# Sheet1.net
KiCad netlist of a schematic drawn in Altium Designer
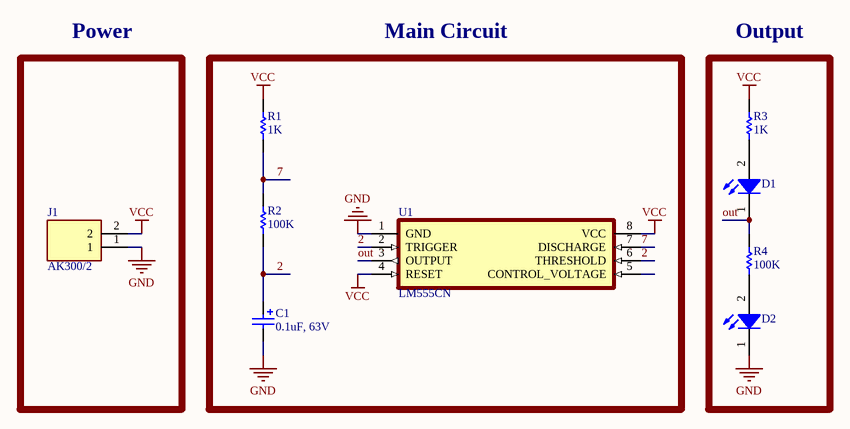
[diagram p0: Sheet1.SchDoc]

(export (version "E")
  (design (tool "Eeschema 10.0.6"))
  (components
    (comp (ref "C1")
      (value "0.1uF, 63V")
      (footprint "WCAP-ATG8_D5H11")
      (description "WCAP-ATG8 Aluminum Electrolytic Capacitor, Radial, THT, D5xH11, 0.1uF, 63V")
      (fields
        (field (name "MANUFACTURER PART NUMBER") "860010772001")
        (field (name "MANUFACTURER") "Wurth Elektronik")
      )
      (libsource (lib "Capacitors Electrolyt") (part "860010772001"))
    )
    (comp (ref "D1")
      (value "15400385A3590")
      (footprint "WL-TIRW_D3.9H5.3")
      (description "WL-TIRW THT Infrared Round Waterclear, D3.9H5.3, 60mW/sr, 1.5V, 35deg")
      (fields (field (name "MANUFACTURER") "Wurth Elektronik"))
      (libsource (lib "WL-TIRW") (part "15400385A3590"))
    )
    (comp (ref "D2")
      (value "15400385A3590")
      (footprint "WL-TIRW_D3.9H5.3")
      (description "WL-TIRW THT Infrared Round Waterclear, D3.9H5.3, 60mW/sr, 1.5V, 35deg")
      (fields (field (name "MANUFACTURER") "Wurth Elektronik"))
      (libsource (lib "WL-TIRW") (part "15400385A3590"))
    )
    (comp (ref "J1")
      (value "AK300/2")
      (footprint "PTR_AK300/2-5,0-GRAU")
      (description "Terminal block; 5mm; angled 45Â°; ways: 2")
      (fields (field (name "MF") "PTR Messtechnik") (field (name "MP") "AK300/2-5,0-GRAU"))
      (libsource (lib "SnapEDAsch") (part "AK300/2-5,0-GRAU"))
    )
    (comp (ref "R1")
      (value "1K")
      (footprint "AXIAL-0.3")
      (description "Resistor")
      (fields (field (name "PUBLISHER") "Altium Limited"))
      (libsource (lib "Miscellaneous Devices") (part "Res1"))
    )
    (comp (ref "R2")
      (value "100K")
      (footprint "AXIAL-0.3")
      (description "Resistor")
      (fields (field (name "PUBLISHER") "Altium Limited"))
      (libsource (lib "Miscellaneous Devices") (part "Res1"))
    )
    (comp (ref "R3")
      (value "1K")
      (footprint "AXIAL-0.3")
      (description "Resistor")
      (fields (field (name "PUBLISHER") "Altium Limited"))
      (libsource (lib "Miscellaneous Devices") (part "Res1"))
    )
    (comp (ref "R4")
      (value "100K")
      (footprint "AXIAL-0.3")
      (description "Resistor")
      (fields (field (name "PUBLISHER") "Altium Limited"))
      (libsource (lib "Miscellaneous Devices") (part "Res1"))
    )
    (comp (ref "U1")
      (value "LM555CN")
      (footprint "DIP794W45P254L959H508Q8")
      (fields (field (name "MP") "LM555CN/NOPB") (field (name "MF") "{'manufacturer': u'ON Semiconductor'}"))
      (libsource (lib "LM555CN") (part "LM555CN"))
    )
  )
  (nets
    (net (code "1") (name "/2") (class "Default")
      (node (ref "C1") (pin "1") (pinfunction "P_1") (pintype "passive"))
      (node (ref "R2") (pin "1") (pinfunction "1_1") (pintype "passive"))
      (node (ref "U1") (pin "2") (pinfunction "TRIGGER_2") (pintype "input"))
      (node (ref "U1") (pin "6") (pinfunction "THRESHOLD_6") (pintype "input"))
    )
    (net (code "2") (name "/7") (class "Default")
      (node (ref "R1") (pin "1") (pinfunction "1_1") (pintype "passive"))
      (node (ref "R2") (pin "2") (pinfunction "2_2") (pintype "passive"))
      (node (ref "U1") (pin "7") (pinfunction "DISCHARGE_7") (pintype "input"))
    )
    (net (code "3") (name "/out") (class "Default")
      (node (ref "D1") (pin "1") (pinfunction "K_1") (pintype "passive"))
      (node (ref "R4") (pin "2") (pinfunction "2_2") (pintype "passive"))
      (node (ref "U1") (pin "3") (pinfunction "OUTPUT_3") (pintype "output"))
    )
    (net (code "4") (name "GND") (class "Default")
      (node (ref "C1") (pin "2") (pinfunction "N_2") (pintype "passive"))
      (node (ref "D2") (pin "1") (pinfunction "K_1") (pintype "passive"))
      (node (ref "J1") (pin "1") (pinfunction "1_1") (pintype "passive"))
      (node (ref "U1") (pin "1") (pinfunction "GND_1") (pintype "power_in"))
    )
    (net (code "5") (name "Net-(D1-A)") (class "Default")
      (node (ref "D1") (pin "2") (pinfunction "A_2") (pintype "passive"))
      (node (ref "R3") (pin "1") (pinfunction "1_1") (pintype "passive"))
    )
    (net (code "6") (name "Net-(D2-A)") (class "Default")
      (node (ref "D2") (pin "2") (pinfunction "A_2") (pintype "passive"))
      (node (ref "R4") (pin "1") (pinfunction "1_1") (pintype "passive"))
    )
    (net (code "7") (name "VCC") (class "Default")
      (node (ref "J1") (pin "2") (pinfunction "2_2") (pintype "passive"))
      (node (ref "R1") (pin "2") (pinfunction "2_2") (pintype "passive"))
      (node (ref "R3") (pin "2") (pinfunction "2_2") (pintype "passive"))
      (node (ref "U1") (pin "4") (pinfunction "RESET_4") (pintype "input"))
      (node (ref "U1") (pin "8") (pinfunction "VCC_8") (pintype "power_in"))
    )
    (net (code "8") (name "unconnected-(U1-CONTROL_VOLTAGE-Pad5)") (class "Default")
      (node (ref "U1") (pin "5") (pinfunction "CONTROL_VOLTAGE_5") (pintype "input"))
    )
  )
)
